# Busswitch_B.net
KiCad netlist of a schematic drawn in Altium Designer
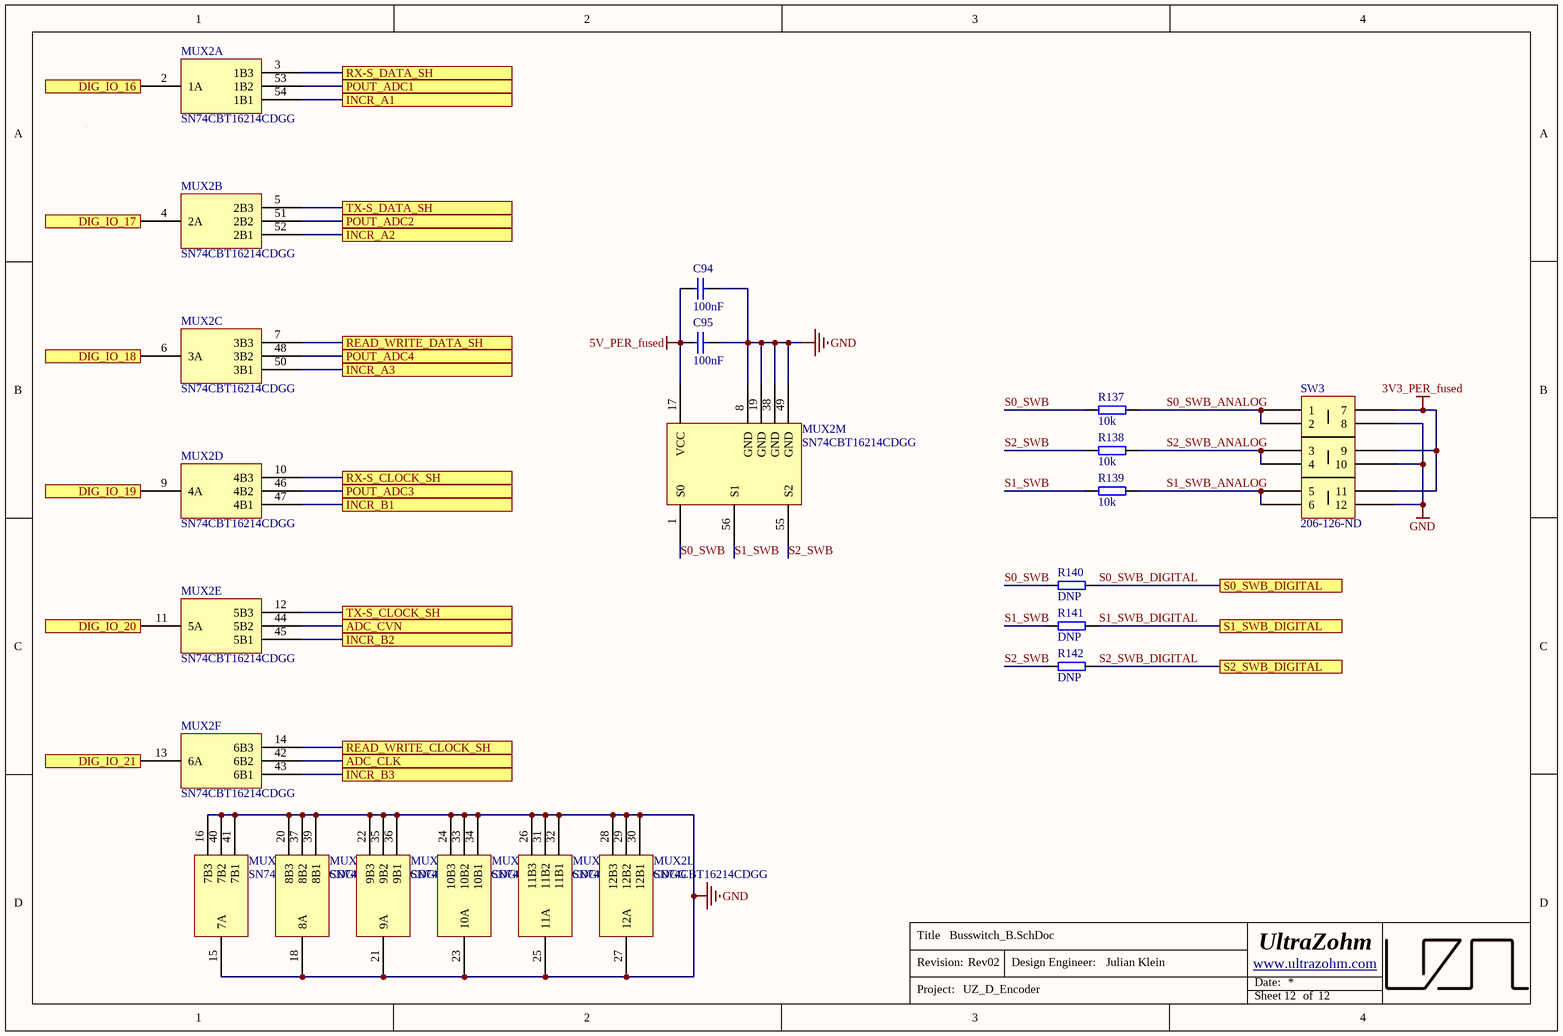
[diagram p0: Busswitch_B.SchDoc]

(export (version "E")
  (design (tool "Eeschema 10.0.6"))
  (components
    (comp (ref "C94")
      (value "100nF")
      (footprint "CAPC1608X07N")
      (fields (field (name "MF") "Würth") (field (name "MPN") "885012206071") (field (name "VOLTAGE") "25V"))
      (libsource (lib "UltraZohm_ADC") (part "Cap_0603"))
    )
    (comp (ref "C95")
      (value "100nF")
      (footprint "CAPC1608X07N")
      (fields (field (name "MF") "Würth") (field (name "MPN") "885012206071") (field (name "VOLTAGE") "25V"))
      (libsource (lib "UltraZohm_ADC") (part "Cap_0603"))
    )
    (comp (ref "MUX2")
      (value "SN74CBT16214CDGG")
      (footprint "TSSOP50P810X120-56N")
      (description "Multiplexer/Demultiplexer Bus Switch 1-Element CMOS 36-IN 56-Pin TSSOP Tube")
      (fields
        (field (name "MANUFACTURER") "Texas Instruments")
        (field (name "SUPPLIER PART NUMBER 1") "SN74CBT16214CDGG")
      )
      (libsource (lib "uz_d_encoder_lib") (part "SN74CBT16214CDGG"))
    )
    (comp (ref "R137")
      (value "10k")
      (footprint "RESC1608X06N")
      (fields (field (name "MF") "Vishay") (field (name "MPN") "CRCW06030000Z0EAC"))
      (libsource (lib "UltraZohm_ADC") (part "R_0603"))
    )
    (comp (ref "R138")
      (value "10k")
      (footprint "RESC1608X06N")
      (fields (field (name "MF") "Vishay") (field (name "MPN") "CRCW06030000Z0EAC"))
      (libsource (lib "UltraZohm_ADC") (part "R_0603"))
    )
    (comp (ref "R139")
      (value "10k")
      (footprint "RESC1608X06N")
      (fields (field (name "MF") "Vishay") (field (name "MPN") "CRCW06030000Z0EAC"))
      (libsource (lib "UltraZohm_ADC") (part "R_0603"))
    )
    (comp (ref "R140")
      (value "DNP")
      (footprint "RESC1608X06N")
      (fields (field (name "MF") "Vishay") (field (name "MPN") "CRCW06030000Z0EAC"))
      (libsource (lib "UltraZohm_ADC") (part "R_0603"))
    )
    (comp (ref "R141")
      (value "DNP")
      (footprint "RESC1608X06N")
      (fields (field (name "MF") "Vishay") (field (name "MPN") "CRCW06030000Z0EAC"))
      (libsource (lib "UltraZohm_ADC") (part "R_0603"))
    )
    (comp (ref "R142")
      (value "DNP")
      (footprint "RESC1608X06N")
      (fields (field (name "MF") "Vishay") (field (name "MPN") "CRCW06030000Z0EAC"))
      (libsource (lib "UltraZohm_ADC") (part "R_0603"))
    )
    (comp (ref "SW3")
      (value "206-126")
      (footprint "206-123")
      (description "Switch DIP OFF ON SPDT 6 Raised Slide 0.05A 24VDC PC Pins 2.54mm Thru-Hole Tube")
      (fields (field (name "MANUFACTURER") "CTS") (field (name "SUPPLIER PART NUMBER 1") "206-126-ND"))
      (libsource (lib "uz_d_encoder_lib") (part "206-126"))
    )
  )
  (nets
    (net (code "1") (name "/ADC_CLK") (class "Default")
      (node (ref "MUX2") (pin "42") (pinfunction "6B2_42") (pintype "passive"))
    )
    (net (code "2") (name "/ADC_CVN") (class "Default")
      (node (ref "MUX2") (pin "44") (pinfunction "5B2_44") (pintype "passive"))
    )
    (net (code "3") (name "/DIG_IO_16") (class "Default")
      (node (ref "MUX2") (pin "2") (pinfunction "1A_2") (pintype "passive"))
    )
    (net (code "4") (name "/DIG_IO_17") (class "Default")
      (node (ref "MUX2") (pin "4") (pinfunction "2A_4") (pintype "passive"))
    )
    (net (code "5") (name "/DIG_IO_18") (class "Default")
      (node (ref "MUX2") (pin "6") (pinfunction "3A_6") (pintype "passive"))
    )
    (net (code "6") (name "/DIG_IO_19") (class "Default")
      (node (ref "MUX2") (pin "9") (pinfunction "4A_9") (pintype "passive"))
    )
    (net (code "7") (name "/DIG_IO_20") (class "Default")
      (node (ref "MUX2") (pin "11") (pinfunction "5A_11") (pintype "passive"))
    )
    (net (code "8") (name "/DIG_IO_21") (class "Default")
      (node (ref "MUX2") (pin "13") (pinfunction "6A_13") (pintype "passive"))
    )
    (net (code "9") (name "/INCR_A1") (class "Default")
      (node (ref "MUX2") (pin "54") (pinfunction "1B1_54") (pintype "passive"))
    )
    (net (code "10") (name "/INCR_A2") (class "Default")
      (node (ref "MUX2") (pin "52") (pinfunction "2B1_52") (pintype "passive"))
    )
    (net (code "11") (name "/INCR_A3") (class "Default")
      (node (ref "MUX2") (pin "50") (pinfunction "3B1_50") (pintype "passive"))
    )
    (net (code "12") (name "/INCR_B1") (class "Default")
      (node (ref "MUX2") (pin "47") (pinfunction "4B1_47") (pintype "passive"))
    )
    (net (code "13") (name "/INCR_B2") (class "Default")
      (node (ref "MUX2") (pin "45") (pinfunction "5B1_45") (pintype "passive"))
    )
    (net (code "14") (name "/INCR_B3") (class "Default")
      (node (ref "MUX2") (pin "43") (pinfunction "6B1_43") (pintype "passive"))
    )
    (net (code "15") (name "/POUT_ADC1") (class "Default")
      (node (ref "MUX2") (pin "53") (pinfunction "1B2_53") (pintype "passive"))
    )
    (net (code "16") (name "/POUT_ADC2") (class "Default")
      (node (ref "MUX2") (pin "51") (pinfunction "2B2_51") (pintype "passive"))
    )
    (net (code "17") (name "/POUT_ADC3") (class "Default")
      (node (ref "MUX2") (pin "46") (pinfunction "4B2_46") (pintype "passive"))
    )
    (net (code "18") (name "/POUT_ADC4") (class "Default")
      (node (ref "MUX2") (pin "48") (pinfunction "3B2_48") (pintype "passive"))
    )
    (net (code "19") (name "/READ_WRITE_CLOCK_SH") (class "Default")
      (node (ref "MUX2") (pin "14") (pinfunction "6B3_14") (pintype "passive"))
    )
    (net (code "20") (name "/READ_WRITE_DATA_SH") (class "Default")
      (node (ref "MUX2") (pin "7") (pinfunction "3B3_7") (pintype "passive"))
    )
    (net (code "21") (name "/RX-S_CLOCK_SH") (class "Default")
      (node (ref "MUX2") (pin "10") (pinfunction "4B3_10") (pintype "passive"))
    )
    (net (code "22") (name "/RX-S_DATA_SH") (class "Default")
      (node (ref "MUX2") (pin "3") (pinfunction "1B3_3") (pintype "passive"))
    )
    (net (code "23") (name "/S0_SWB") (class "Default")
      (node (ref "MUX2") (pin "1") (pinfunction "S0_1") (pintype "passive"))
      (node (ref "R137") (pin "2") (pintype "passive"))
      (node (ref "R140") (pin "2") (pintype "passive"))
    )
    (net (code "24") (name "/S0_SWB_ANALOG") (class "Default")
      (node (ref "R137") (pin "1") (pintype "passive"))
      (node (ref "SW3") (pin "1") (pinfunction "1_1") (pintype "passive"))
      (node (ref "SW3") (pin "2") (pinfunction "2_2") (pintype "passive"))
    )
    (net (code "25") (name "/S0_SWB_DIGITAL") (class "Default")
      (node (ref "R140") (pin "1") (pintype "passive"))
    )
    (net (code "26") (name "/S1_SWB") (class "Default")
      (node (ref "MUX2") (pin "56") (pinfunction "S1_56") (pintype "passive"))
      (node (ref "R139") (pin "2") (pintype "passive"))
      (node (ref "R141") (pin "2") (pintype "passive"))
    )
    (net (code "27") (name "/S1_SWB_ANALOG") (class "Default")
      (node (ref "R139") (pin "1") (pintype "passive"))
      (node (ref "SW3") (pin "5") (pinfunction "5_5") (pintype "passive"))
      (node (ref "SW3") (pin "6") (pinfunction "6_6") (pintype "passive"))
    )
    (net (code "28") (name "/S1_SWB_DIGITAL") (class "Default")
      (node (ref "R141") (pin "1") (pintype "passive"))
    )
    (net (code "29") (name "/S2_SWB") (class "Default")
      (node (ref "MUX2") (pin "55") (pinfunction "S2_55") (pintype "passive"))
      (node (ref "R138") (pin "2") (pintype "passive"))
      (node (ref "R142") (pin "2") (pintype "passive"))
    )
    (net (code "30") (name "/S2_SWB_ANALOG") (class "Default")
      (node (ref "R138") (pin "1") (pintype "passive"))
      (node (ref "SW3") (pin "3") (pinfunction "3_3") (pintype "passive"))
      (node (ref "SW3") (pin "4") (pinfunction "4_4") (pintype "passive"))
    )
    (net (code "31") (name "/S2_SWB_DIGITAL") (class "Default")
      (node (ref "R142") (pin "1") (pintype "passive"))
    )
    (net (code "32") (name "/TX-S_CLOCK_SH") (class "Default")
      (node (ref "MUX2") (pin "12") (pinfunction "5B3_12") (pintype "passive"))
    )
    (net (code "33") (name "/TX-S_DATA_SH") (class "Default")
      (node (ref "MUX2") (pin "5") (pinfunction "2B3_5") (pintype "passive"))
    )
    (net (code "34") (name "3V3_PER_fused") (class "Default")
      (node (ref "SW3") (pin "11") (pinfunction "11_11") (pintype "passive"))
      (node (ref "SW3") (pin "7") (pinfunction "7_7") (pintype "passive"))
      (node (ref "SW3") (pin "9") (pinfunction "9_9") (pintype "passive"))
    )
    (net (code "35") (name "5V_PER_fused") (class "Default")
      (node (ref "C94") (pin "1") (pinfunction "1_1") (pintype "passive"))
      (node (ref "C95") (pin "1") (pinfunction "1_1") (pintype "passive"))
      (node (ref "MUX2") (pin "17") (pinfunction "VCC_17") (pintype "passive"))
    )
    (net (code "36") (name "GND") (class "Default")
      (node (ref "C94") (pin "2") (pinfunction "2_2") (pintype "passive"))
      (node (ref "C95") (pin "2") (pinfunction "2_2") (pintype "passive"))
      (node (ref "MUX2") (pin "15") (pinfunction "7A_15") (pintype "passive"))
      (node (ref "MUX2") (pin "16") (pinfunction "7B3_16") (pintype "passive"))
      (node (ref "MUX2") (pin "18") (pinfunction "8A_18") (pintype "passive"))
      (node (ref "MUX2") (pin "19") (pinfunction "GND_19") (pintype "passive"))
      (node (ref "MUX2") (pin "20") (pinfunction "8B3_20") (pintype "passive"))
      (node (ref "MUX2") (pin "21") (pinfunction "9A_21") (pintype "passive"))
      (node (ref "MUX2") (pin "22") (pinfunction "9B3_22") (pintype "passive"))
      (node (ref "MUX2") (pin "23") (pinfunction "10A_23") (pintype "passive"))
      (node (ref "MUX2") (pin "24") (pinfunction "10B3_24") (pintype "passive"))
      (node (ref "MUX2") (pin "25") (pinfunction "11A_25") (pintype "passive"))
      (node (ref "MUX2") (pin "26") (pinfunction "11B3_26") (pintype "passive"))
      (node (ref "MUX2") (pin "27") (pinfunction "12A_27") (pintype "passive"))
      (node (ref "MUX2") (pin "28") (pinfunction "12B3_28") (pintype "passive"))
      (node (ref "MUX2") (pin "29") (pinfunction "12B2_29") (pintype "passive"))
      (node (ref "MUX2") (pin "30") (pinfunction "12B1_30") (pintype "passive"))
      (node (ref "MUX2") (pin "31") (pinfunction "11B2_31") (pintype "passive"))
      (node (ref "MUX2") (pin "32") (pinfunction "11B1_32") (pintype "passive"))
      (node (ref "MUX2") (pin "33") (pinfunction "10B2_33") (pintype "passive"))
      (node (ref "MUX2") (pin "34") (pinfunction "10B1_34") (pintype "passive"))
      (node (ref "MUX2") (pin "35") (pinfunction "9B2_35") (pintype "passive"))
      (node (ref "MUX2") (pin "36") (pinfunction "9B1_36") (pintype "passive"))
      (node (ref "MUX2") (pin "37") (pinfunction "8B2_37") (pintype "passive"))
      (node (ref "MUX2") (pin "38") (pinfunction "GND_38") (pintype "passive"))
      (node (ref "MUX2") (pin "39") (pinfunction "8B1_39") (pintype "passive"))
      (node (ref "MUX2") (pin "40") (pinfunction "7B2_40") (pintype "passive"))
      (node (ref "MUX2") (pin "41") (pinfunction "7B1_41") (pintype "passive"))
      (node (ref "MUX2") (pin "49") (pinfunction "GND_49") (pintype "passive"))
      (node (ref "MUX2") (pin "8") (pinfunction "GND_8") (pintype "passive"))
      (node (ref "SW3") (pin "10") (pinfunction "10_10") (pintype "passive"))
      (node (ref "SW3") (pin "12") (pinfunction "12_12") (pintype "passive"))
      (node (ref "SW3") (pin "8") (pinfunction "8_8") (pintype "passive"))
    )
  )
)
